# Relais2-N_Channel_MOSFET-V003.net
KiCad netlist of a schematic drawn in EAGLE
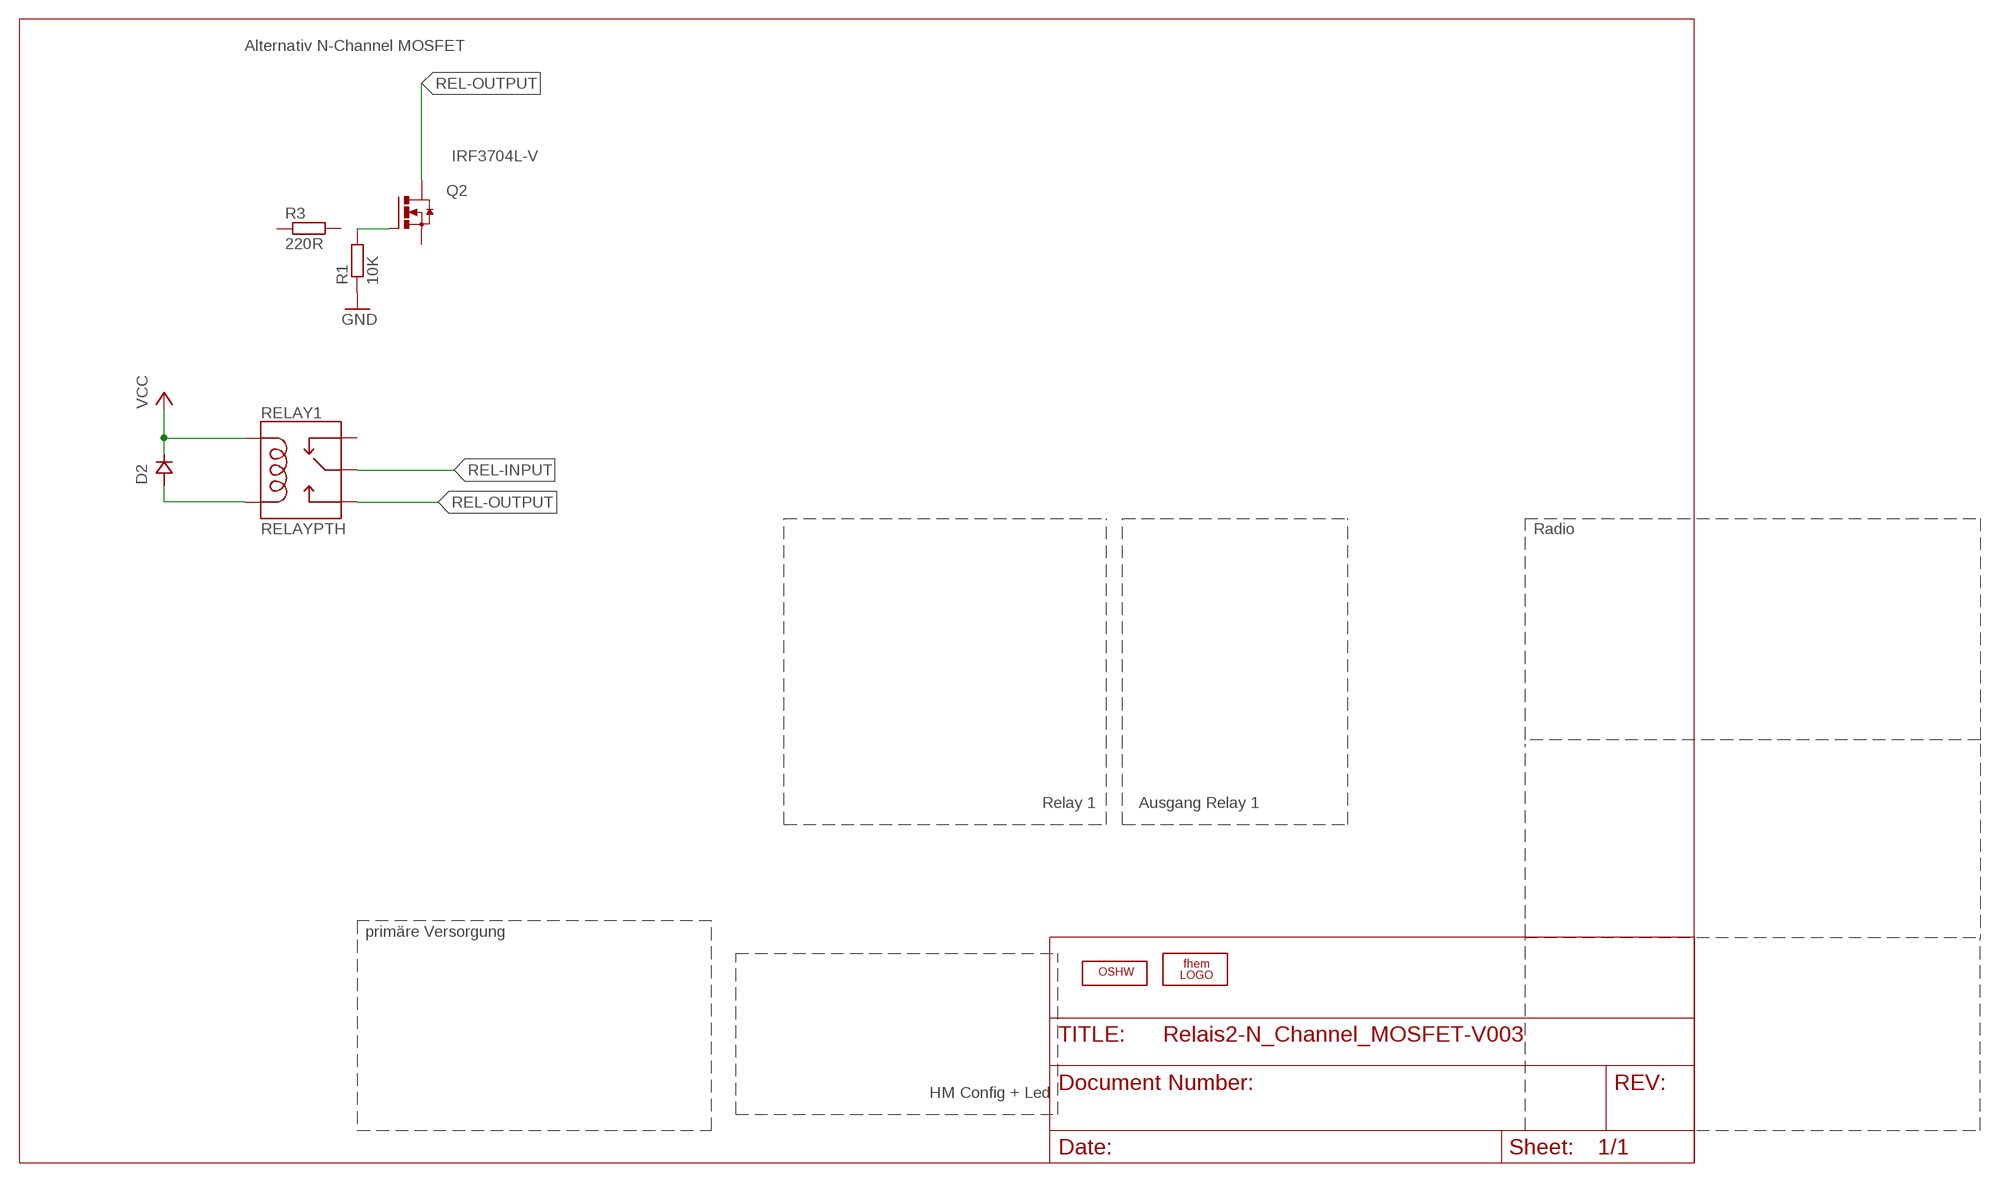
[diagram p0: schematic, sheet 1]

(export (version "E")
  (design (tool "Eeschema 10.0.6"))
  (components
    (comp (ref "D2")
      (value "SS14")
      (footprint "eagle-import:DO214")
      (libsource (lib "eagle-import") (part "SS14"))
    )
    (comp (ref "LOGO2")
      (value "LOGO_OSHWX0070")
      (footprint "eagle-import:OSHW_6X70")
      (libsource (lib "eagle-import") (part "LOGO_OSHWX0070"))
    )
    (comp (ref "Q2")
      (value "IRF3704L-V")
      (footprint "eagle-import:TO262-V")
      (libsource (lib "eagle-import") (part "IRF3704L-V"))
    )
    (comp (ref "R1")
      (value "10K")
      (footprint "eagle-import:R0805_SMALL_GAP")
      (libsource (lib "eagle-import") (part "R0805_SMALL_GAP"))
    )
    (comp (ref "R3")
      (value "220R")
      (footprint "eagle-import:R0805_SMALL_GAP")
      (libsource (lib "eagle-import") (part "R0805_SMALL_GAP"))
    )
    (comp (ref "RELAY1")
      (value "RELAYPTH")
      (footprint "eagle-import:SRD-05VDC-SL-C")
      (libsource (lib "eagle-import") (part "RELAYPTH"))
    )
    (comp (ref "U$2")
      (value "LOGO_FHEMSTOP")
      (footprint "eagle-import:LOGO_FHEM_3X3_STOP")
      (libsource (lib "eagle-import") (part "LOGO_FHEMSTOP"))
    )
  )
  (nets
    (net (code "1") (name "GND") (class "Default")
      (node (ref "R1") (pin "1") (pinfunction "1_1") (pintype "passive"))
    )
    (net (code "2") (name "Net-(D2-PadANODE)") (class "Default")
      (node (ref "D2") (pin "ANODE") (pinfunction "ANODE_ANODE") (pintype "bidirectional"))
      (node (ref "RELAY1") (pin "COIL0") (pinfunction "COIL0_COIL0") (pintype "bidirectional"))
    )
    (net (code "3") (name "Net-(Q2-G)") (class "Default")
      (node (ref "Q2") (pin "1") (pinfunction "G_1") (pintype "passive"))
      (node (ref "R1") (pin "2") (pinfunction "2_2") (pintype "passive"))
    )
    (net (code "4") (name "REL-INPUT") (class "Default")
      (node (ref "RELAY1") (pin "SWCOMMON") (pinfunction "SWCOMMON_SWCOMMON") (pintype "bidirectional"))
    )
    (net (code "5") (name "REL-OUTPUT") (class "Default")
      (node (ref "Q2") (pin "2") (pinfunction "D_2") (pintype "passive"))
      (node (ref "RELAY1") (pin "SWOPEN") (pinfunction "SWOPEN_SWOPEN") (pintype "bidirectional"))
    )
    (net (code "6") (name "VCC") (class "Default")
      (node (ref "D2") (pin "CATHODE") (pinfunction "CATHODE_CATHODE") (pintype "bidirectional"))
      (node (ref "RELAY1") (pin "COIL1") (pinfunction "COIL1_COIL1") (pintype "bidirectional"))
    )
    (net (code "7") (name "unconnected-(Q2-S-Pad3)") (class "Default")
      (node (ref "Q2") (pin "3") (pinfunction "S_3") (pintype "passive"))
    )
    (net (code "8") (name "unconnected-(R3-Pad1)") (class "Default")
      (node (ref "R3") (pin "1") (pinfunction "1_1") (pintype "passive"))
    )
    (net (code "9") (name "unconnected-(R3-Pad2)") (class "Default")
      (node (ref "R3") (pin "2") (pinfunction "2_2") (pintype "passive"))
    )
    (net (code "10") (name "unconnected-(RELAY1-SWCLOSE-PadSWCLOSED)") (class "Default")
      (node (ref "RELAY1") (pin "SWCLOSED") (pinfunction "SWCLOSE_SWCLOSED") (pintype "bidirectional"))
    )
  )
)
